# main.net
KiCad netlist of a schematic drawn in Altium Designer
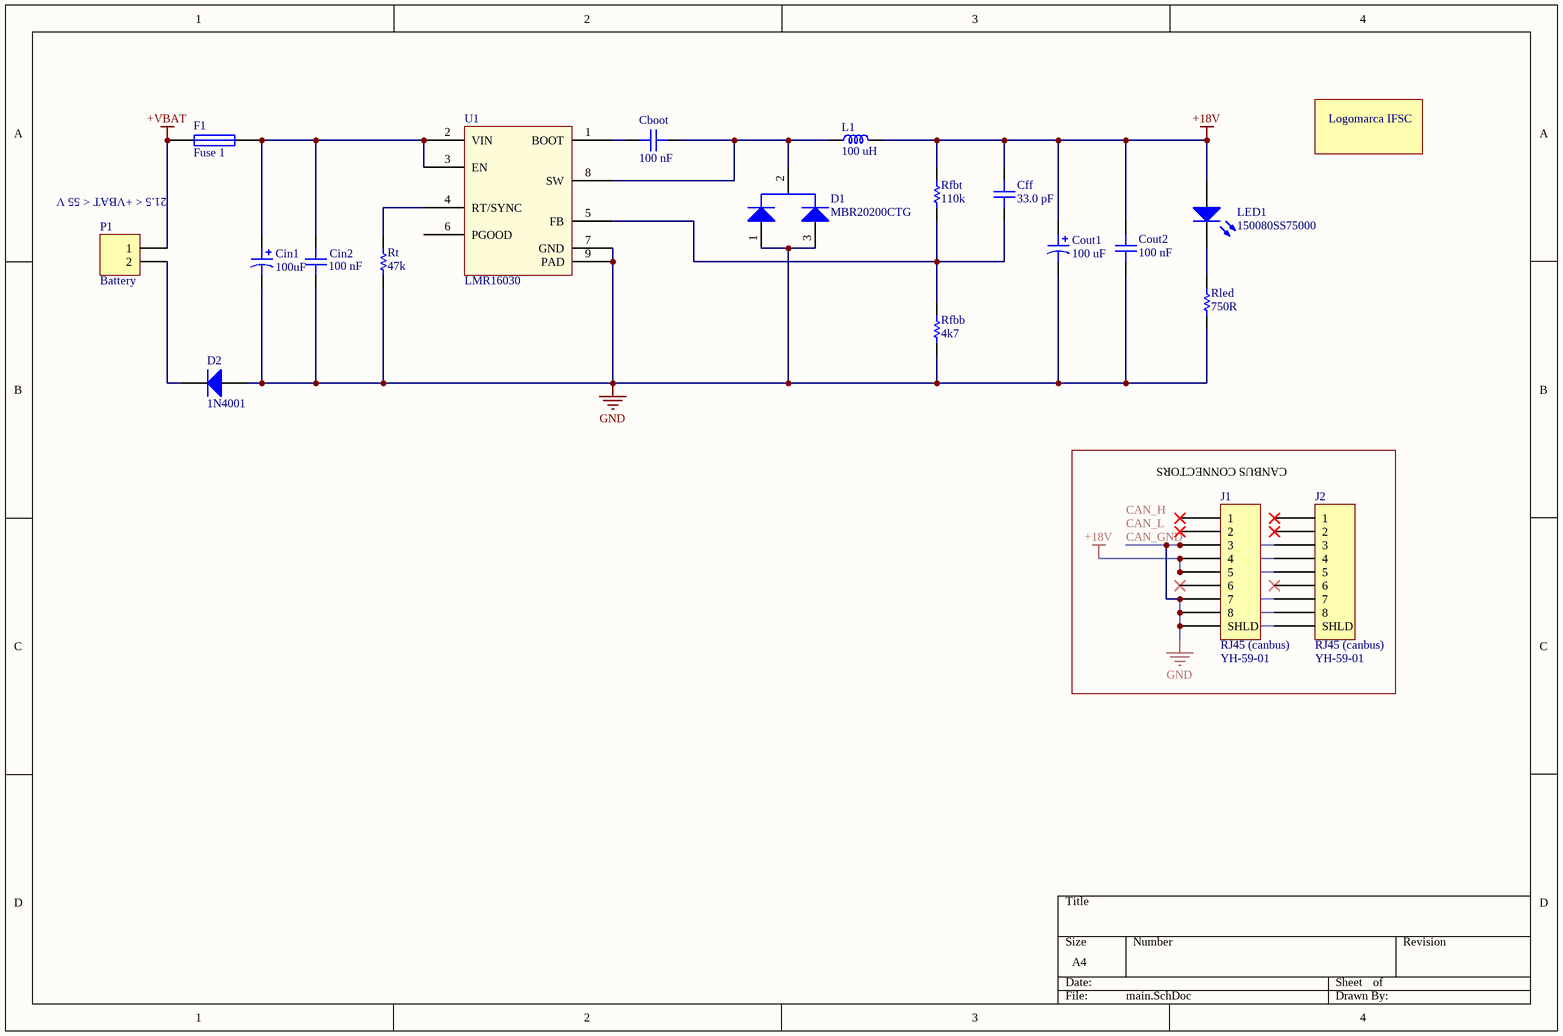
[diagram p0: main.SchDoc]

(export (version "E")
  (design (tool "Eeschema 10.0.6"))
  (components
    (comp (ref "Cboot")
      (value "100 nF")
      (footprint "0805C")
      (description "Capacitor")
      (fields (field (name "VOLTAGE") "25 V") (field (name "PUBLISHER") "Altium Limited"))
      (libsource (lib "passive") (part "Capacitor"))
    )
    (comp (ref "Cff")
      (value "33.0 pF")
      (footprint "0805C")
      (description "Capacitor")
      (fields (field (name "VOLTAGE") "16 V") (field (name "PUBLISHER") "Altium Limited"))
      (libsource (lib "passive") (part "Capacitor"))
    )
    (comp (ref "Cin1")
      (value "100uF")
      (footprint "CP-RAD-12.5mm-35.0mm-5.0mm")
      (description "Solid Aluminum Capacitor with Organic Semiconductor Electrolyte: 100uF, 10V, Bulk Pack")
      (fields (field (name "VOLTAGE") "100V") (field (name "PUBLISHER") "Altium Limited"))
      (libsource (lib "passive") (part "CapacitorPol"))
    )
    (comp (ref "Cin2")
      (value "100 nF")
      (footprint "0805C")
      (description "Capacitor")
      (fields (field (name "VOLTAGE") "100 V") (field (name "PUBLISHER") "Altium Limited"))
      (libsource (lib "passive") (part "Capacitor"))
    )
    (comp (ref "Cout1")
      (value "100 uF")
      (footprint "CP-RAD-12.5mm-35.0mm-5.0mm")
      (description "Solid Aluminum Capacitor with Organic Semiconductor Electrolyte: 100uF, 10V, Bulk Pack")
      (fields (field (name "VOLTAGE") "25 V") (field (name "PUBLISHER") "Altium Limited"))
      (libsource (lib "passive") (part "CapacitorPol"))
    )
    (comp (ref "Cout2")
      (value "100 nF")
      (footprint "0805C")
      (description "Capacitor")
      (fields (field (name "VOLTAGE") "25 V") (field (name "PUBLISHER") "Altium Limited"))
      (libsource (lib "passive") (part "Capacitor"))
    )
    (comp (ref "D1")
      (value "MBR20200CTG")
      (footprint "TO-220-deitado")
      (description "SWITCHMODE(TM) Power Rectifier, Dual Schottky Rectifiers, 3-Pin TO-220, Pb-Free, Tube")
      (fields (field (name "MANUFACTURER") "On Semiconductor"))
      (libsource (lib "Altium Content Vault") (part "ONSC-D-A1K2A3-3_B"))
    )
    (comp (ref "D2")
      (value "1N4001")
      (footprint "DIO10.46-5.3x2.8")
      (description "1 Amp General Purpose Rectifier")
      (fields (field (name "PUBLISHER") "Altium Limited"))
      (libsource (lib "Miscellaneous Devices") (part "Diode 1N4001"))
    )
    (comp (ref "F1")
      (value "Fuse 1")
      (footprint "5x20")
      (description "Fuse")
      (fields (field (name "PUBLISHER") "Altium Limited"))
      (libsource (lib "Miscellaneous Devices") (part "Fuse 1"))
    )
    (comp (ref "J1")
      (value "RJ45 (canbus)")
      (footprint "ASSMANN A-2004-2-4-LP/FS")
      (description "YH-59-01")
      (fields (field (name "ALTIUM_VALUE") "YH-59-01"))
      (libsource (lib "Connectors") (part "Modular Jack with Shield"))
    )
    (comp (ref "J2")
      (value "RJ45 (canbus)")
      (footprint "ASSMANN A-2004-2-4-LP/FS")
      (description "YH-59-01")
      (fields (field (name "ALTIUM_VALUE") "YH-59-01"))
      (libsource (lib "Connectors") (part "Modular Jack with Shield"))
    )
    (comp (ref "L1")
      (value "100 uH")
      (footprint "Toroldal D:20, H:10")
      (description "Inductor")
      (libsource (lib "passive") (part "Inductor"))
    )
    (comp (ref "LED1")
      (value "150080SS75000")
      (footprint "0805R")
      (description "SMD mono-color Chip LED, WL-SMCW, Super Red")
      (fields (field (name "MANUFACTURER") "Wuerth Elektronik"))
      (libsource (lib "Altium Content Vault") (part "WE-LED_K1A2-2"))
    )
    (comp (ref "P1")
      (value "Battery")
      (footprint "KRE_2")
      (description "Terminal Block 1x2")
      (libsource (lib "connector") (part "KRE_2"))
    )
    (comp (ref "Rfbb")
      (value "4k7")
      (footprint "0805R")
      (description "Resistor")
      (fields
        (field (name "POWER") "1/8 W")
        (field (name "TOLERANCE") "5%")
        (field (name "PUBLISHER") "Altium Limited")
      )
      (libsource (lib "passive") (part "Resistor"))
    )
    (comp (ref "Rfbt")
      (value "110k")
      (footprint "0805R")
      (description "Resistor")
      (fields
        (field (name "POWER") "1/8 W")
        (field (name "TOLERANCE") "5%")
        (field (name "PUBLISHER") "Altium Limited")
      )
      (libsource (lib "passive") (part "Resistor"))
    )
    (comp (ref "Rled")
      (value "750R")
      (footprint "0805R")
      (description "Resistor")
      (fields
        (field (name "POWER") "1/8 W")
        (field (name "TOLERANCE") "5%")
        (field (name "PUBLISHER") "Altium Limited")
      )
      (libsource (lib "passive") (part "Resistor"))
    )
    (comp (ref "Rt")
      (value "47k")
      (footprint "0805R")
      (description "Resistor")
      (fields
        (field (name "POWER") "1/8 W")
        (field (name "TOLERANCE") "5%")
        (field (name "PUBLISHER") "Altium Limited")
      )
      (libsource (lib "passive") (part "Resistor"))
    )
    (comp (ref "U1")
      (value "LMR16030")
      (footprint "lmr16030")
      (libsource (lib "LMR16030") (part "Component_1"))
    )
    (comp (ref "X1")
      (value "Logomarca IFSC")
      (footprint "IFSC_SILK")
      (libsource (lib "R2R - Nova") (part "logomarcaIFSC"))
    )
  )
  (nets
    (net (code "1") (name "+18V") (class "Default")
      (node (ref "Cff") (pin "2") (pinfunction "2_2") (pintype "passive"))
      (node (ref "Cout1") (pin "1") (pinfunction "1_1") (pintype "passive"))
      (node (ref "Cout2") (pin "1") (pinfunction "1_1") (pintype "passive"))
      (node (ref "J1") (pin "4") (pinfunction "4_4") (pintype "passive"))
      (node (ref "J1") (pin "5") (pinfunction "5_5") (pintype "passive"))
      (node (ref "J2") (pin "4") (pinfunction "4_4") (pintype "passive"))
      (node (ref "J2") (pin "5") (pinfunction "5_5") (pintype "passive"))
      (node (ref "L1") (pin "2") (pinfunction "2_2") (pintype "passive"))
      (node (ref "LED1") (pin "2") (pinfunction "A_2") (pintype "passive"))
      (node (ref "Rfbt") (pin "2") (pinfunction "2_2") (pintype "passive"))
    )
    (net (code "2") (name "+VBAT") (class "Default")
      (node (ref "F1") (pin "1") (pinfunction "1_1") (pintype "passive"))
      (node (ref "P1") (pin "1") (pinfunction "1_1") (pintype "passive"))
    )
    (net (code "5") (name "GND") (class "Default")
      (node (ref "Cin1") (pin "2") (pinfunction "2_2") (pintype "passive"))
      (node (ref "Cin2") (pin "2") (pinfunction "2_2") (pintype "passive"))
      (node (ref "Cout1") (pin "2") (pinfunction "2_2") (pintype "passive"))
      (node (ref "Cout2") (pin "2") (pinfunction "2_2") (pintype "passive"))
      (node (ref "D1") (pin "1") (pinfunction "A1_1") (pintype "passive"))
      (node (ref "D1") (pin "3") (pinfunction "A2_3") (pintype "passive"))
      (node (ref "D2") (pin "1") (pinfunction "A_1") (pintype "passive"))
      (node (ref "J1") (pin "3") (pinfunction "3_3") (pintype "passive"))
      (node (ref "J1") (pin "7") (pinfunction "7_7") (pintype "passive"))
      (node (ref "J1") (pin "8") (pinfunction "8_8") (pintype "passive"))
      (node (ref "J1") (pin "S") (pinfunction "SHLD_S") (pintype "passive"))
      (node (ref "J2") (pin "3") (pinfunction "3_3") (pintype "passive"))
      (node (ref "J2") (pin "7") (pinfunction "7_7") (pintype "passive"))
      (node (ref "J2") (pin "8") (pinfunction "8_8") (pintype "passive"))
      (node (ref "J2") (pin "S") (pinfunction "SHLD_S") (pintype "passive"))
      (node (ref "Rfbb") (pin "1") (pinfunction "1_1") (pintype "passive"))
      (node (ref "Rled") (pin "1") (pinfunction "1_1") (pintype "passive"))
      (node (ref "Rt") (pin "2") (pinfunction "2_2") (pintype "passive"))
      (node (ref "U1") (pin "7") (pinfunction "GND_7") (pintype "passive"))
      (node (ref "U1") (pin "9") (pinfunction "PAD_9") (pintype "passive"))
    )
    (net (code "6") (name "Net-(D1-K)") (class "Default")
      (node (ref "Cboot") (pin "1") (pinfunction "1_1") (pintype "passive"))
      (node (ref "D1") (pin "2") (pinfunction "K_2") (pintype "passive"))
      (node (ref "L1") (pin "1") (pinfunction "1_1") (pintype "passive"))
      (node (ref "U1") (pin "8") (pinfunction "SW_8") (pintype "passive"))
    )
    (net (code "7") (name "Net-(D2-K)") (class "Default")
      (node (ref "D2") (pin "2") (pinfunction "K_2") (pintype "passive"))
      (node (ref "P1") (pin "2") (pinfunction "2_2") (pintype "passive"))
    )
    (net (code "8") (name "Net-(LED1-K)") (class "Default")
      (node (ref "LED1") (pin "1") (pinfunction "K_1") (pintype "passive"))
      (node (ref "Rled") (pin "2") (pinfunction "2_2") (pintype "passive"))
    )
    (net (code "9") (name "Net-(U1-BOOT)") (class "Default")
      (node (ref "Cboot") (pin "2") (pinfunction "2_2") (pintype "passive"))
      (node (ref "U1") (pin "1") (pinfunction "BOOT_1") (pintype "passive"))
    )
    (net (code "10") (name "Net-(U1-EN)") (class "Default")
      (node (ref "Cin1") (pin "1") (pinfunction "1_1") (pintype "passive"))
      (node (ref "Cin2") (pin "1") (pinfunction "1_1") (pintype "passive"))
      (node (ref "F1") (pin "2") (pinfunction "2_2") (pintype "passive"))
      (node (ref "U1") (pin "2") (pinfunction "VIN_2") (pintype "passive"))
      (node (ref "U1") (pin "3") (pinfunction "EN_3") (pintype "passive"))
    )
    (net (code "11") (name "Net-(U1-FB)") (class "Default")
      (node (ref "Cff") (pin "1") (pinfunction "1_1") (pintype "passive"))
      (node (ref "Rfbb") (pin "2") (pinfunction "2_2") (pintype "passive"))
      (node (ref "Rfbt") (pin "1") (pinfunction "1_1") (pintype "passive"))
      (node (ref "U1") (pin "5") (pinfunction "FB_5") (pintype "passive"))
    )
    (net (code "12") (name "Net-(U1-RT{slash}SYNC)") (class "Default")
      (node (ref "Rt") (pin "1") (pinfunction "1_1") (pintype "passive"))
      (node (ref "U1") (pin "4") (pinfunction "RT/SYNC_4") (pintype "passive"))
    )
    (net (code "13") (name "unconnected-(J1-Pad1)") (class "Default")
      (node (ref "J1") (pin "1") (pinfunction "1_1") (pintype "passive+no_connect"))
    )
    (net (code "14") (name "unconnected-(J1-Pad2)") (class "Default")
      (node (ref "J1") (pin "2") (pinfunction "2_2") (pintype "passive+no_connect"))
    )
    (net (code "15") (name "unconnected-(J1-Pad6)") (class "Default")
      (node (ref "J1") (pin "6") (pinfunction "6_6") (pintype "passive+no_connect"))
    )
    (net (code "16") (name "unconnected-(J2-Pad1)") (class "Default")
      (node (ref "J2") (pin "1") (pinfunction "1_1") (pintype "passive+no_connect"))
    )
    (net (code "17") (name "unconnected-(J2-Pad2)") (class "Default")
      (node (ref "J2") (pin "2") (pinfunction "2_2") (pintype "passive+no_connect"))
    )
    (net (code "18") (name "unconnected-(J2-Pad6)") (class "Default")
      (node (ref "J2") (pin "6") (pinfunction "6_6") (pintype "passive+no_connect"))
    )
    (net (code "19") (name "unconnected-(U1-PGOOD-Pad6)") (class "Default")
      (node (ref "U1") (pin "6") (pinfunction "PGOOD_6") (pintype "passive"))
    )
  )
)
